# circuit_r2.net
KiCad netlist of a schematic drawn in EAGLE
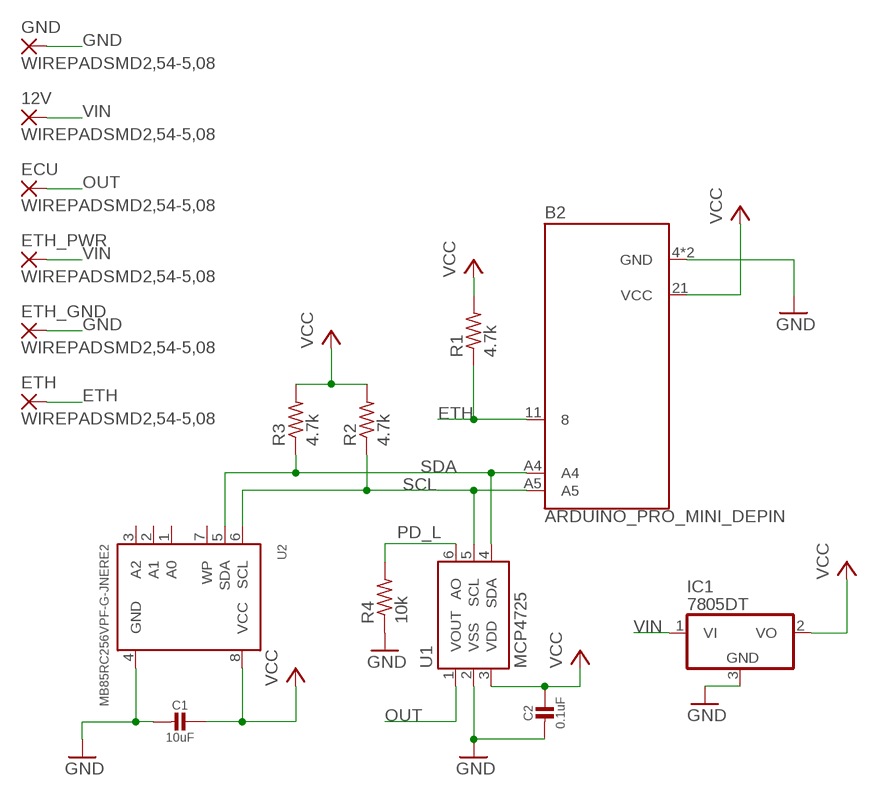
[diagram p0: schematic, sheet 1]

(export (version "E")
  (design (tool "Eeschema 10.0.6"))
  (components
    (comp (ref "12V")
      (value "WIREPADSMD2,54-5,08")
      (footprint "eagle-import:SMD2,54-5,08")
      (libsource (lib "eagle-import") (part "WIREPADSMD2,54-5,08"))
    )
    (comp (ref "B2")
      (value "ARDUINO_PRO_MINI_DEPIN")
      (footprint "eagle-import:ARDUINO_PRO_MINI")
      (libsource (lib "eagle-import") (part "ARDUINO_PRO_MINI_DEPIN"))
    )
    (comp (ref "C1")
      (value "10uF")
      (footprint "eagle-import:_0805MP")
      (libsource (lib "eagle-import") (part "CAP_CERAMIC_0805MP"))
    )
    (comp (ref "C2")
      (value "0.1uF")
      (footprint "eagle-import:_0805MP")
      (libsource (lib "eagle-import") (part "CAP_CERAMIC_0805MP"))
    )
    (comp (ref "ECU")
      (value "WIREPADSMD2,54-5,08")
      (footprint "eagle-import:SMD2,54-5,08")
      (libsource (lib "eagle-import") (part "WIREPADSMD2,54-5,08"))
    )
    (comp (ref "ETH")
      (value "WIREPADSMD2,54-5,08")
      (footprint "eagle-import:SMD2,54-5,08")
      (libsource (lib "eagle-import") (part "WIREPADSMD2,54-5,08"))
    )
    (comp (ref "ETH_GND")
      (value "WIREPADSMD2,54-5,08")
      (footprint "eagle-import:SMD2,54-5,08")
      (libsource (lib "eagle-import") (part "WIREPADSMD2,54-5,08"))
    )
    (comp (ref "ETH_PWR")
      (value "WIREPADSMD2,54-5,08")
      (footprint "eagle-import:SMD2,54-5,08")
      (libsource (lib "eagle-import") (part "WIREPADSMD2,54-5,08"))
    )
    (comp (ref "GND")
      (value "WIREPADSMD2,54-5,08")
      (footprint "eagle-import:SMD2,54-5,08")
      (libsource (lib "eagle-import") (part "WIREPADSMD2,54-5,08"))
    )
    (comp (ref "IC1")
      (value "7805DT")
      (footprint "eagle-import:TO252")
      (libsource (lib "eagle-import") (part "78DT05"))
    )
    (comp (ref "R1")
      (value "4.7k")
      (footprint "eagle-import:R0603")
      (libsource (lib "eagle-import") (part "R-US_R0603"))
    )
    (comp (ref "R2")
      (value "4.7k")
      (footprint "eagle-import:R0603")
      (libsource (lib "eagle-import") (part "R-US_R0603"))
    )
    (comp (ref "R3")
      (value "4.7k")
      (footprint "eagle-import:R0603")
      (libsource (lib "eagle-import") (part "R-US_R0603"))
    )
    (comp (ref "R4")
      (value "10k")
      (footprint "eagle-import:R0603")
      (libsource (lib "eagle-import") (part "R-US_R0603"))
    )
    (comp (ref "U1")
      (value "MCP4725")
      (footprint "eagle-import:SOT23-6")
      (libsource (lib "eagle-import") (part "MCP4725SOT-23"))
    )
    (comp (ref "U2")
      (value "MB85RC256VPF-G-JNERE2")
      (footprint "eagle-import:SOIC8_208MIL")
      (libsource (lib "eagle-import") (part "FRAM_SOIC8_I2C"))
    )
  )
  (nets
    (net (code "1") (name "/ETH") (class "Default")
      (node (ref "B2") (pin "11") (pinfunction "8_11") (pintype "bidirectional"))
      (node (ref "ETH") (pin "1") (pinfunction "P_1") (pintype "passive"))
      (node (ref "R1") (pin "1") (pinfunction "1_1") (pintype "passive"))
    )
    (net (code "2") (name "/OUT") (class "Default")
      (node (ref "ECU") (pin "1") (pinfunction "P_1") (pintype "passive"))
      (node (ref "U1") (pin "1") (pinfunction "VOUT_1") (pintype "bidirectional"))
    )
    (net (code "3") (name "/PD_L") (class "Default")
      (node (ref "R4") (pin "2") (pinfunction "2_2") (pintype "passive"))
      (node (ref "U1") (pin "6") (pinfunction "AO_6") (pintype "bidirectional"))
    )
    (net (code "4") (name "/SCL") (class "Default")
      (node (ref "B2") (pin "A5") (pinfunction "A5_A5") (pintype "bidirectional"))
      (node (ref "R2") (pin "1") (pinfunction "1_1") (pintype "passive"))
      (node (ref "U1") (pin "5") (pinfunction "SCL_5") (pintype "bidirectional"))
      (node (ref "U2") (pin "6") (pinfunction "SCL_6") (pintype "input"))
    )
    (net (code "5") (name "/SDA") (class "Default")
      (node (ref "B2") (pin "A4") (pinfunction "A4_A4") (pintype "bidirectional"))
      (node (ref "R3") (pin "1") (pinfunction "1_1") (pintype "passive"))
      (node (ref "U1") (pin "4") (pinfunction "SDA_4") (pintype "bidirectional"))
      (node (ref "U2") (pin "5") (pinfunction "SDA_5") (pintype "bidirectional"))
    )
    (net (code "6") (name "/VIN") (class "Default")
      (node (ref "12V") (pin "1") (pinfunction "P_1") (pintype "passive"))
      (node (ref "ETH_PWR") (pin "1") (pinfunction "P_1") (pintype "passive"))
      (node (ref "IC1") (pin "1") (pinfunction "VI_1") (pintype "input"))
    )
    (net (code "7") (name "GND") (class "Default")
      (node (ref "B2") (pin "23") (pinfunction "GND_23") (pintype "power_in"))
      (node (ref "B2") (pin "4") (pinfunction "GND_4") (pintype "power_in"))
      (node (ref "C1") (pin "2") (pinfunction "2_2") (pintype "passive"))
      (node (ref "C2") (pin "2") (pinfunction "2_2") (pintype "passive"))
      (node (ref "ETH_GND") (pin "1") (pinfunction "P_1") (pintype "passive"))
      (node (ref "GND") (pin "1") (pinfunction "P_1") (pintype "passive"))
      (node (ref "IC1") (pin "3") (pinfunction "GND_3") (pintype "passive"))
      (node (ref "R4") (pin "1") (pinfunction "1_1") (pintype "passive"))
      (node (ref "U1") (pin "2") (pinfunction "VSS_2") (pintype "bidirectional"))
      (node (ref "U2") (pin "4") (pinfunction "GND_4") (pintype "power_in"))
    )
    (net (code "8") (name "VCC") (class "Default")
      (node (ref "B2") (pin "21") (pinfunction "VCC_21") (pintype "power_in"))
      (node (ref "C1") (pin "1") (pinfunction "1_1") (pintype "passive"))
      (node (ref "C2") (pin "1") (pinfunction "1_1") (pintype "passive"))
      (node (ref "IC1") (pin "2") (pinfunction "VO_2") (pintype "passive"))
      (node (ref "R1") (pin "2") (pinfunction "2_2") (pintype "passive"))
      (node (ref "R2") (pin "2") (pinfunction "2_2") (pintype "passive"))
      (node (ref "R3") (pin "2") (pinfunction "2_2") (pintype "passive"))
      (node (ref "U1") (pin "3") (pinfunction "VDD_3") (pintype "bidirectional"))
      (node (ref "U2") (pin "8") (pinfunction "VCC_8") (pintype "power_in"))
    )
    (net (code "9") (name "unconnected-(U2-A0-Pad1)") (class "Default")
      (node (ref "U2") (pin "1") (pinfunction "A0_1") (pintype "input"))
    )
    (net (code "10") (name "unconnected-(U2-A1-Pad2)") (class "Default")
      (node (ref "U2") (pin "2") (pinfunction "A1_2") (pintype "input"))
    )
    (net (code "11") (name "unconnected-(U2-A2-Pad3)") (class "Default")
      (node (ref "U2") (pin "3") (pinfunction "A2_3") (pintype "input"))
    )
    (net (code "12") (name "unconnected-(U2-WP-Pad7)") (class "Default")
      (node (ref "U2") (pin "7") (pinfunction "WP_7") (pintype "input"))
    )
  )
)
